# GUAGE.net
KiCad netlist of a schematic drawn in Altium Designer
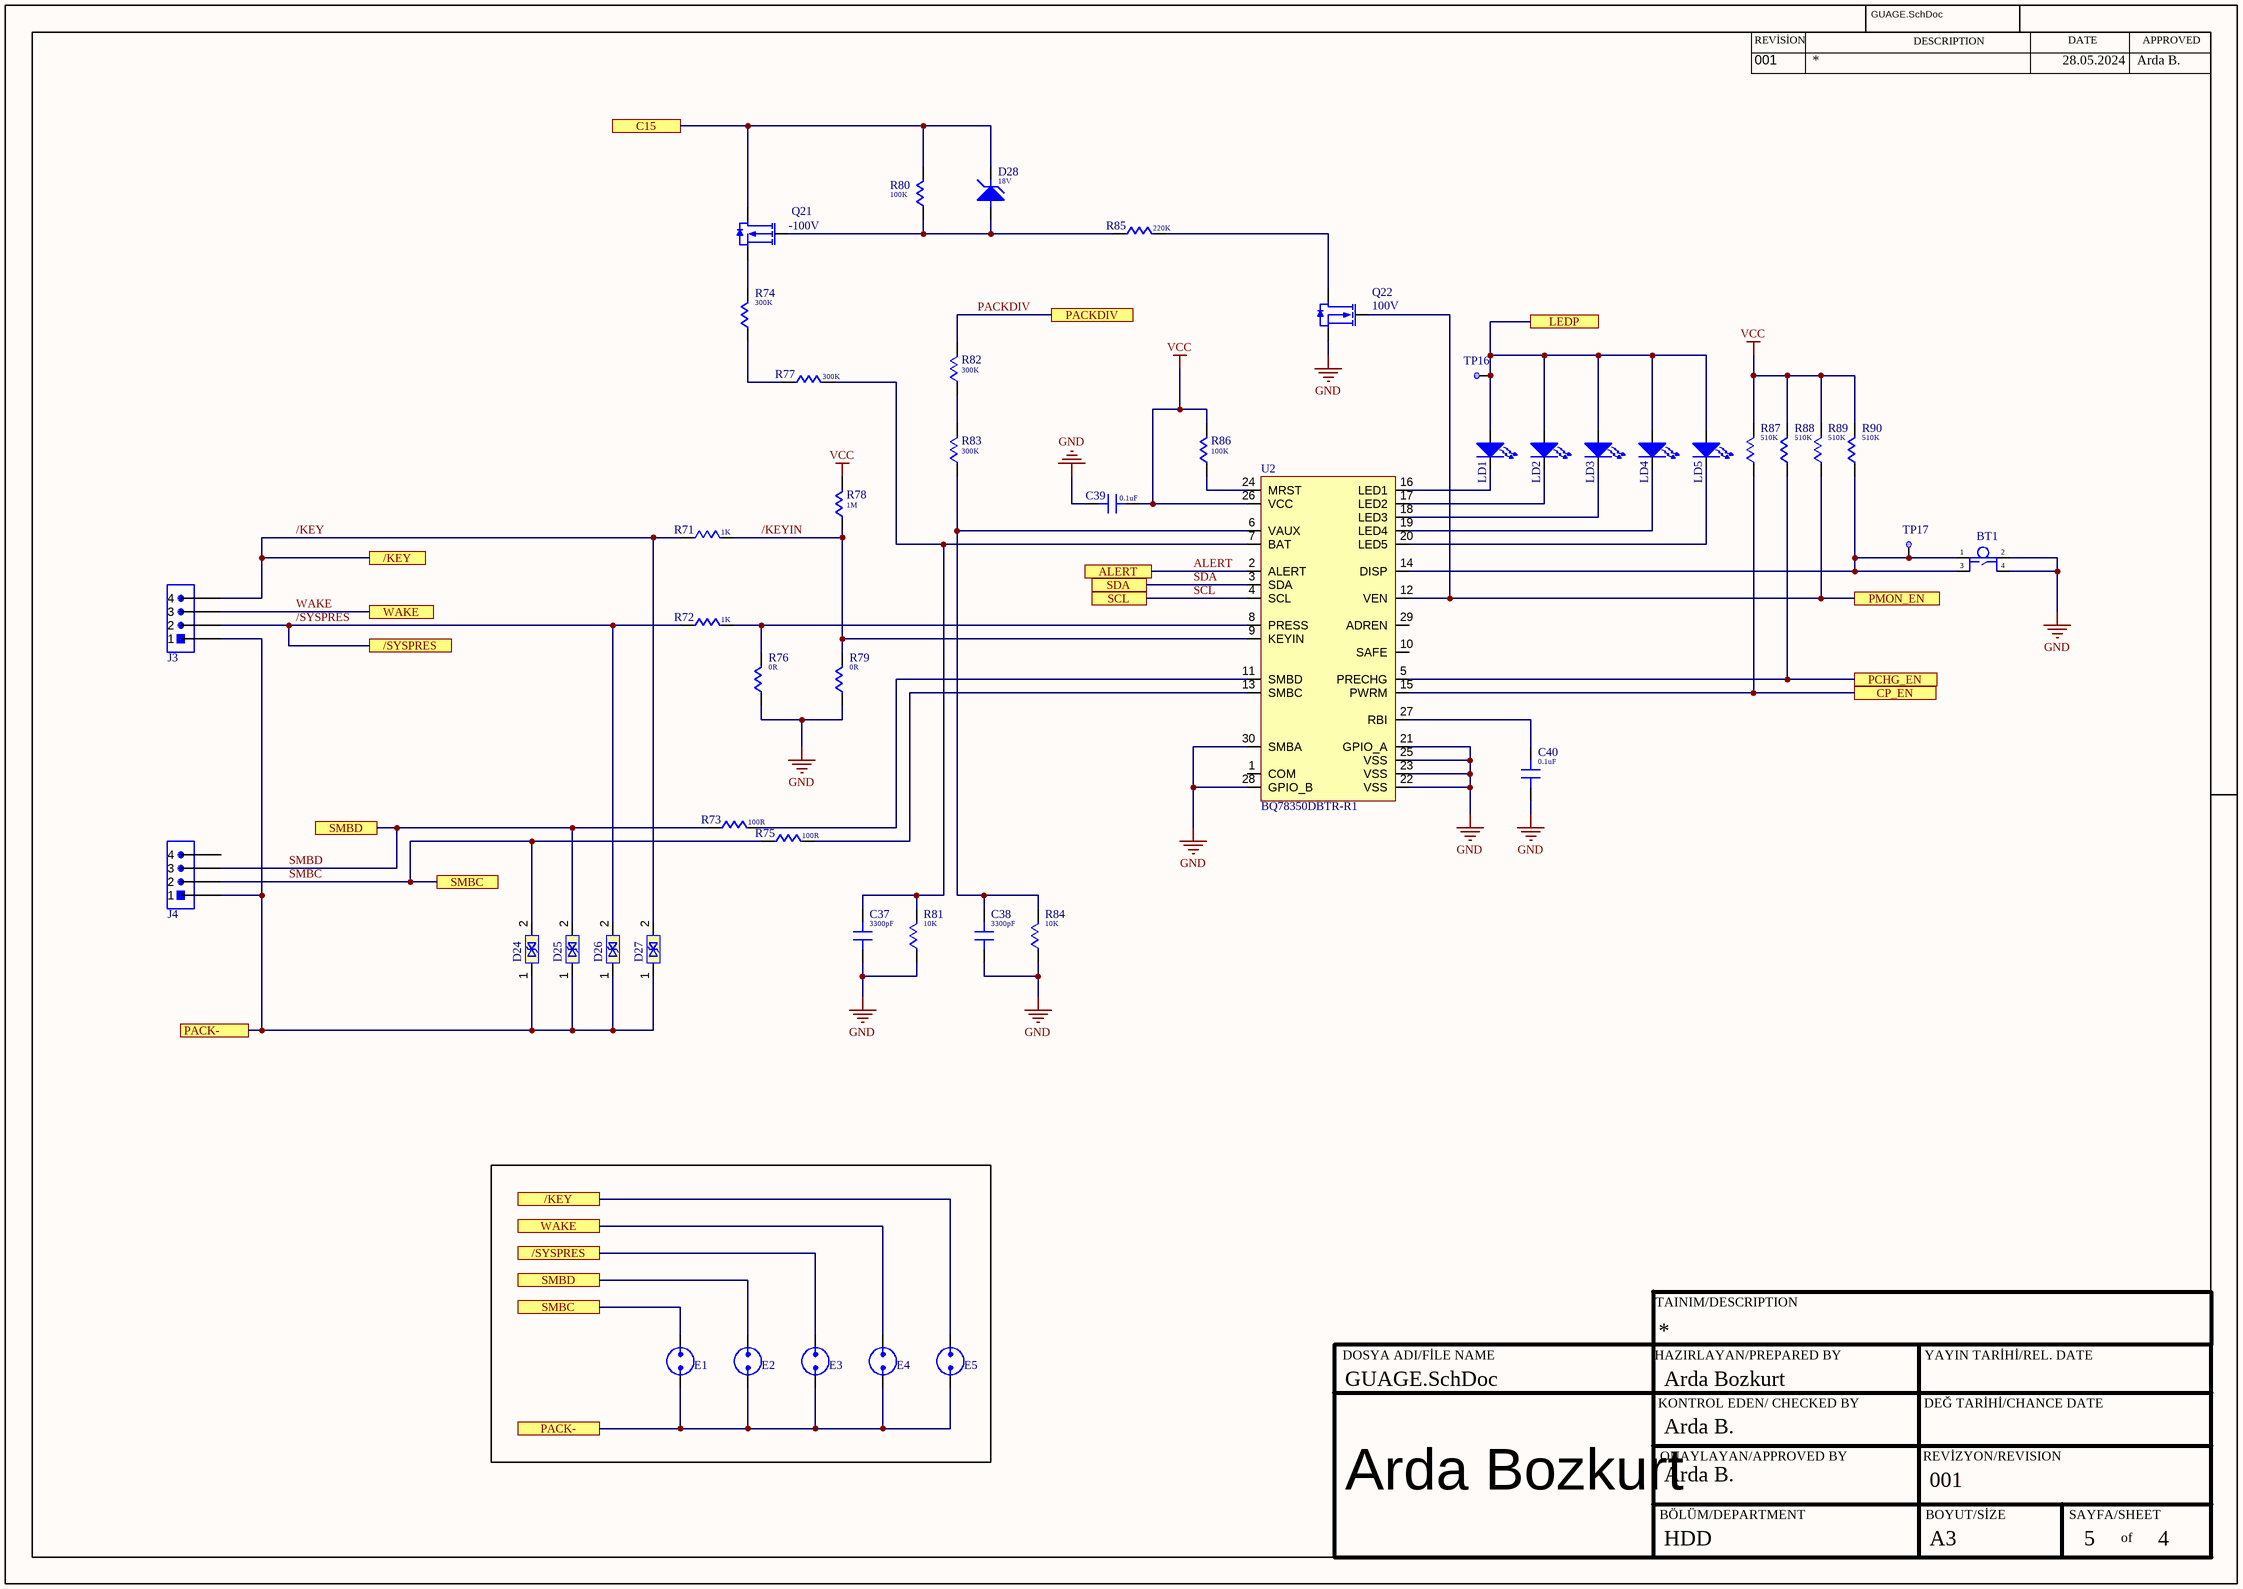
[diagram p0: GUAGE.SchDoc]

(export (version "E")
  (design (tool "Eeschema 10.0.6"))
  (components
    (comp (ref "BT1")
      (value "1977223-6")
      (footprint "BUTTOM")
      (description "Pushbutton Switch, SPST, Momentary, 0.05A, 24VDC, Solder Terminal, Panel Mount")
      (fields
        (field (name "MANUFACTURER") "TE Connectivity")
        (field (name "MANUFACTURER PART NUMBER") "FSM4JSMA")
      )
      (libsource (lib "BMS_Lib") (part "BT_SWITCH_TACTILE_0.05A_24V"))
    )
    (comp (ref "C37")
      (value "3300pF")
      (footprint "C_0603")
      (description "Multilayer Ceramic Capacitor, 0.1 uF, 100 V, ± 10%, X7R, 0603 [1608 Metric]")
      (fields
        (field (name "MANUFACTURER") "Murata")
        (field (name "MANUFACTURER PART NUMBER") "GRM188R72A104KA35D")
      )
      (libsource (lib "BMS_Lib") (part "C_3300pF_0603_25V"))
    )
    (comp (ref "C38")
      (value "3300pF")
      (footprint "C_0603")
      (description "Multilayer Ceramic Capacitor, 0.1 uF, 100 V, ± 10%, X7R, 0603 [1608 Metric]")
      (fields
        (field (name "MANUFACTURER") "Murata")
        (field (name "MANUFACTURER PART NUMBER") "GRM188R72A104KA35D")
      )
      (libsource (lib "BMS_Lib") (part "C_3300pF_0603_25V"))
    )
    (comp (ref "C39")
      (value "0.1uF")
      (footprint "C_0603")
      (description "Ceramic Capacitor, Multilayer, Ceramic, 50V, 10% -Tol, X7R, 15% Tc, 0.1Uf, Surface Mount, 0603")
      (fields
        (field (name "MANUFACTURER") "TDK")
        (field (name "MANUFACTURER PART NUMBER") "C1608X7R1H104K080AA")
      )
      (libsource (lib "BMS_Lib") (part "C_0.1uF_0603_50V"))
    )
    (comp (ref "C40")
      (value "0.1uF")
      (footprint "C_0603")
      (description "Ceramic Capacitor, Multilayer, Ceramic, 50V, 10% -Tol, X7R, 15% Tc, 0.1Uf, Surface Mount, 0603")
      (fields
        (field (name "MANUFACTURER") "TDK")
        (field (name "MANUFACTURER PART NUMBER") "C1608X7R1H104K080AA")
      )
      (libsource (lib "BMS_Lib") (part "C_0.1uF_0603_50V"))
    )
    (comp (ref "D24")
      (value "TPD1E10B06DPYT")
      (footprint "ESD_X1SON")
      (description "12-pF, ±5.5V, ±30-kV ESD protection diode in 0402 and SOD-523 package 2-X1SON -40 to 125")
      (fields (field (name "MANUFACTURER") "Texas Instruments"))
      (libsource (lib "BMS_Lib") (part "ESD_TVS_DİODE_5.5VWM_14VC_2X1SON"))
    )
    (comp (ref "D25")
      (value "TPD1E10B06DPYT")
      (footprint "ESD_X1SON")
      (description "12-pF, ±5.5V, ±30-kV ESD protection diode in 0402 and SOD-523 package 2-X1SON -40 to 125")
      (fields (field (name "MANUFACTURER") "Texas Instruments"))
      (libsource (lib "BMS_Lib") (part "ESD_TVS_DİODE_5.5VWM_14VC_2X1SON"))
    )
    (comp (ref "D26")
      (value "TPD1E10B06DPYT")
      (footprint "ESD_X1SON")
      (description "12-pF, ±5.5V, ±30-kV ESD protection diode in 0402 and SOD-523 package 2-X1SON -40 to 125")
      (fields (field (name "MANUFACTURER") "Texas Instruments"))
      (libsource (lib "BMS_Lib") (part "ESD_TVS_DİODE_5.5VWM_14VC_2X1SON"))
    )
    (comp (ref "D27")
      (value "TPD1E10B06DPYT")
      (footprint "ESD_X1SON")
      (description "12-pF, ±5.5V, ±30-kV ESD protection diode in 0402 and SOD-523 package 2-X1SON -40 to 125")
      (fields (field (name "MANUFACTURER") "Texas Instruments"))
      (libsource (lib "BMS_Lib") (part "ESD_TVS_DİODE_5.5VWM_14VC_2X1SON"))
    )
    (comp (ref "D28")
      (value "18V")
      (footprint "D_SOD323")
      (description "Diode Zener Single 18V 5% 200mW Automotive 2-Pin SOD-323 T/R")
      (fields
        (field (name "MANUFACTURER") "Diodes")
        (field (name "MANUFACTURER PART NUMBER") "MMSZ5248BS-7-F")
      )
      (libsource (lib "BMS_Lib") (part "D_ZENER_18V_SOD323"))
    )
    (comp (ref "E1")
      (value "SPARKGAP")
      (footprint "SPARK_GARP")
      (description "Spark Gap")
      (libsource (lib "BMS_Lib") (part "E_Spark_Gap"))
    )
    (comp (ref "E2")
      (value "SPARKGAP")
      (footprint "SPARK_GARP")
      (description "Spark Gap")
      (libsource (lib "BMS_Lib") (part "E_Spark_Gap"))
    )
    (comp (ref "E3")
      (value "SPARKGAP")
      (footprint "SPARK_GARP")
      (description "Spark Gap")
      (libsource (lib "BMS_Lib") (part "E_Spark_Gap"))
    )
    (comp (ref "E4")
      (value "SPARKGAP")
      (footprint "SPARK_GARP")
      (description "Spark Gap")
      (libsource (lib "BMS_Lib") (part "E_Spark_Gap"))
    )
    (comp (ref "E5")
      (value "SPARKGAP")
      (footprint "SPARK_GARP")
      (description "Spark Gap")
      (libsource (lib "BMS_Lib") (part "E_Spark_Gap"))
    )
    (comp (ref "J3")
      (value "0022053041")
      (footprint "CONN_4")
      (description "KK 254 Solid Header, Right-Angle, with Friction Lock, 4 Circuits, Tin (Sn) Plating")
      (fields (field (name "MANUFACTURER") "Molex") (field (name "MANUFACTURER PART NUMBER") "22-05-3041"))
      (libsource (lib "BMS_Lib") (part "J_CONN_4POS_2.54MM"))
    )
    (comp (ref "J4")
      (value "0022053041")
      (footprint "CONN_4")
      (description "KK 254 Solid Header, Right-Angle, with Friction Lock, 4 Circuits, Tin (Sn) Plating")
      (fields (field (name "MANUFACTURER") "Molex") (field (name "MANUFACTURER PART NUMBER") "22-05-3041"))
      (libsource (lib "BMS_Lib") (part "J_CONN_4POS_2.54MM"))
    )
    (comp (ref "LD1")
      (value "LTST-C190GKT")
      (footprint "LED_0603")
      (description "LED Uni-Color Green 565nm 2-Pin Chip LED T/R")
      (fields (field (name "MANUFACTURER") "Vishay Lite-On") (field (name "VOLTAGE") "2V"))
      (libsource (lib "BMS_Lib") (part "LED_GREEN_0603"))
    )
    (comp (ref "LD2")
      (value "LTST-C190GKT")
      (footprint "LED_0603")
      (description "LED Uni-Color Green 565nm 2-Pin Chip LED T/R")
      (fields (field (name "MANUFACTURER") "Vishay Lite-On") (field (name "VOLTAGE") "2V"))
      (libsource (lib "BMS_Lib") (part "LED_GREEN_0603"))
    )
    (comp (ref "LD3")
      (value "LTST-C190GKT")
      (footprint "LED_0603")
      (description "LED Uni-Color Green 565nm 2-Pin Chip LED T/R")
      (fields (field (name "MANUFACTURER") "Vishay Lite-On") (field (name "VOLTAGE") "2V"))
      (libsource (lib "BMS_Lib") (part "LED_GREEN_0603"))
    )
    (comp (ref "LD4")
      (value "LTST-C190GKT")
      (footprint "LED_0603")
      (description "LED Uni-Color Green 565nm 2-Pin Chip LED T/R")
      (fields (field (name "MANUFACTURER") "Vishay Lite-On") (field (name "VOLTAGE") "2V"))
      (libsource (lib "BMS_Lib") (part "LED_GREEN_0603"))
    )
    (comp (ref "LD5")
      (value "LTST-C190GKT")
      (footprint "LED_0603")
      (description "LED Uni-Color Green 565nm 2-Pin Chip LED T/R")
      (fields (field (name "MANUFACTURER") "Vishay Lite-On") (field (name "VOLTAGE") "2V"))
      (libsource (lib "BMS_Lib") (part "LED_GREEN_0603"))
    )
    (comp (ref "Q21")
      (value "ZXMP10A13FTA")
      (footprint "Q_SOT23-3")
      (description "P-Channel 100 V 1 Ohm Surface Mount Enhancement Mode MOSFET - SOT-23")
      (fields (field (name "MANUFACTURER") "Diodes Zetex") (field (name "VOLTAGE RATING (DC)") "-100V"))
      (libsource (lib "BMS_Lib") (part "Q_MOSFET_100V_SOT23-3_1"))
    )
    (comp (ref "Q22")
      (value "BSS123")
      (footprint "Q_SOT23-3")
      (description "Transistor MOSFET Negative Channel 100 Volt 0.17A 3-Pin SOT-23")
      (fields (field (name "MANUFACTURER") "ON Semiconductor / Fairchild") (field (name "VOLTAGE") "100V"))
      (libsource (lib "BMS_Lib") (part "Q_MOSFET_100V_SOT23-3"))
    )
    (comp (ref "R71")
      (value "1K")
      (footprint "R_0603")
      (description "SMD Chip Resistor, 1 kOhm, ± 5%, 100 mW, 0603 [1608 Metric], Thick Film, General Purpose")
      (fields
        (field (name "MANUFACTURER") "Vishay Dale")
        (field (name "MANUFACTURER PART NUMBER") "CRCW06031K00JNEA")
      )
      (libsource (lib "BMS_Lib") (part "R_1K_%5_1/10W_0603"))
    )
    (comp (ref "R72")
      (value "1K")
      (footprint "R_0603")
      (description "SMD Chip Resistor, 1 kOhm, ± 5%, 100 mW, 0603 [1608 Metric], Thick Film, General Purpose")
      (fields
        (field (name "MANUFACTURER") "Vishay Dale")
        (field (name "MANUFACTURER PART NUMBER") "CRCW06031K00JNEA")
      )
      (libsource (lib "BMS_Lib") (part "R_1K_%5_1/10W_0603"))
    )
    (comp (ref "R73")
      (value "100R")
      (footprint "R_0603")
      (description "SMD Chip Resistor, 100 Ohm, ± 5%, 100 mW, 0603 [1608 Metric], Thick Film, General Purpose")
      (fields
        (field (name "MANUFACTURER") "Vishay Dale")
        (field (name "MANUFACTURER PART NUMBER") "CRCW0603100RJNEA")
      )
      (libsource (lib "BMS_Lib") (part "R_100OHM_%5_1/10W_0603"))
    )
    (comp (ref "R74")
      (value "300K")
      (footprint "R_0603")
      (description "Res Thin Film 0603 300K Ohm 0.1% 0.1W(1/10W) ±25ppm/C Sulfur Resistant Pad SMD Automotive T/R")
      (fields
        (field (name "MANUFACTURER") "Susumu")
        (field (name "MANUFACTURER PART NUMBER") "RG1608P-304-B-T5")
      )
      (libsource (lib "BMS_Lib") (part "R_300K_%0.1_1/10W_0603"))
    )
    (comp (ref "R75")
      (value "100R")
      (footprint "R_0603")
      (description "SMD Chip Resistor, 100 Ohm, ± 5%, 100 mW, 0603 [1608 Metric], Thick Film, General Purpose")
      (fields
        (field (name "MANUFACTURER") "Vishay Dale")
        (field (name "MANUFACTURER PART NUMBER") "CRCW0603100RJNEA")
      )
      (libsource (lib "BMS_Lib") (part "R_100OHM_%5_1/10W_0603"))
    )
    (comp (ref "R76")
      (value "0R")
      (footprint "R_0603")
      (description "Zero Ohm Resistor, Jumper, 0603 [1608 Metric], Thick Film, 330 mW, 5 A, Surface Mount")
      (fields
        (field (name "MANUFACTURER") "Vishay Dale")
        (field (name "MANUFACTURER PART NUMBER") "CRCW06030000Z0EAHP")
      )
      (libsource (lib "BMS_Lib") (part "R_0OHM_1/10W_0603"))
    )
    (comp (ref "R77")
      (value "300K")
      (footprint "R_0603")
      (description "Res Thin Film 0603 300K Ohm 0.1% 0.1W(1/10W) ±25ppm/C Sulfur Resistant Pad SMD Automotive T/R")
      (fields
        (field (name "MANUFACTURER") "Susumu")
        (field (name "MANUFACTURER PART NUMBER") "RG1608P-304-B-T5")
      )
      (libsource (lib "BMS_Lib") (part "R_300K_%0.1_1/10W_0603"))
    )
    (comp (ref "R78")
      (value "1M")
      (footprint "R_0603")
      (description "SMD Chip Resistor, 1 MOhm, ± 5%, 100 mW, 0603 [1608 Metric], Thick Film, General Purpose")
      (fields
        (field (name "MANUFACTURER") "Vishay Dale")
        (field (name "MANUFACTURER PART NUMBER") "CRCW06031M00JNEA")
      )
      (libsource (lib "BMS_Lib") (part "R_1M_%5_1/10W_0603"))
    )
    (comp (ref "R79")
      (value "0R")
      (footprint "R_0603")
      (description "Zero Ohm Resistor, Jumper, 0603 [1608 Metric], Thick Film, 330 mW, 5 A, Surface Mount")
      (fields
        (field (name "MANUFACTURER") "Vishay Dale")
        (field (name "MANUFACTURER PART NUMBER") "CRCW06030000Z0EAHP")
      )
      (libsource (lib "BMS_Lib") (part "R_0OHM_1/10W_0603"))
    )
    (comp (ref "R80")
      (value "100K")
      (footprint "R_0603")
      (description "SMD Chip Resistor, 100 kOhm, ± 5%, 100 mW, 0603 [1608 Metric], Thick Film, General Purpose")
      (fields
        (field (name "MANUFACTURER") "Vishay")
        (field (name "MANUFACTURER PART NUMBER") "CRCW0603100KJNEA")
      )
      (libsource (lib "BMS_Lib") (part "R_100K_%5_1/10W_0603"))
    )
    (comp (ref "R81")
      (value "10K")
      (footprint "R_0603")
      (description "Res Thin Film 0603 10K Ohm 0.1% 0.1W(1/10W) ±25ppm/C Sulfur Resistant Pad SMD Automotive T/R")
      (fields
        (field (name "MANUFACTURER") "Susumu")
        (field (name "MANUFACTURER PART NUMBER") "RG1608P-103-B-T5")
      )
      (libsource (lib "BMS_Lib") (part "R_10K_%0.1_1/10W_0603"))
    )
    (comp (ref "R82")
      (value "300K")
      (footprint "R_0603")
      (description "Res Thin Film 0603 300K Ohm 0.1% 0.1W(1/10W) ±25ppm/C Sulfur Resistant Pad SMD Automotive T/R")
      (fields
        (field (name "MANUFACTURER") "Susumu")
        (field (name "MANUFACTURER PART NUMBER") "RG1608P-304-B-T5")
      )
      (libsource (lib "BMS_Lib") (part "R_300K_%0.1_1/10W_0603"))
    )
    (comp (ref "R83")
      (value "300K")
      (footprint "R_0603")
      (description "Res Thin Film 0603 300K Ohm 0.1% 0.1W(1/10W) ±25ppm/C Sulfur Resistant Pad SMD Automotive T/R")
      (fields
        (field (name "MANUFACTURER") "Susumu")
        (field (name "MANUFACTURER PART NUMBER") "RG1608P-304-B-T5")
      )
      (libsource (lib "BMS_Lib") (part "R_300K_%0.1_1/10W_0603"))
    )
    (comp (ref "R84")
      (value "10K")
      (footprint "R_0603")
      (description "Res Thin Film 0603 10K Ohm 0.1% 0.1W(1/10W) ±25ppm/C Sulfur Resistant Pad SMD Automotive T/R")
      (fields
        (field (name "MANUFACTURER") "Susumu")
        (field (name "MANUFACTURER PART NUMBER") "RG1608P-103-B-T5")
      )
      (libsource (lib "BMS_Lib") (part "R_10K_%0.1_1/10W_0603"))
    )
    (comp (ref "R85")
      (value "220K")
      (footprint "R_0603")
      (description "SMD Chip Resistor, 220 kOhm, ± 5%, 100 mW, 0603 [1608 Metric], Thick Film, General Purpose")
      (fields
        (field (name "MANUFACTURER") "Vishay Dale")
        (field (name "MANUFACTURER PART NUMBER") "CRCW0603220KJNEA")
      )
      (libsource (lib "BMS_Lib") (part "R_220K_%5_1/10W_0603"))
    )
    (comp (ref "R86")
      (value "100K")
      (footprint "R_0603")
      (description "SMD Chip Resistor, 100 kOhm, ± 5%, 100 mW, 0603 [1608 Metric], Thick Film, General Purpose")
      (fields
        (field (name "MANUFACTURER") "Vishay")
        (field (name "MANUFACTURER PART NUMBER") "CRCW0603100KJNEA")
      )
      (libsource (lib "BMS_Lib") (part "R_100K_%5_1/10W_0603"))
    )
    (comp (ref "R87")
      (value "510K")
      (footprint "R_0603")
      (description "SMD Chip Resistor, 510 kOhm, ± 5%, 100 mW, 0603 [1608 Metric], Thick Film, General Purpose")
      (fields
        (field (name "MANUFACTURER") "Vishay Dale")
        (field (name "MANUFACTURER PART NUMBER") "CRCW0603510KJNEA")
      )
      (libsource (lib "BMS_Lib") (part "R_510K_%5_1/10W_0603"))
    )
    (comp (ref "R88")
      (value "510K")
      (footprint "R_0603")
      (description "SMD Chip Resistor, 510 kOhm, ± 5%, 100 mW, 0603 [1608 Metric], Thick Film, General Purpose")
      (fields
        (field (name "MANUFACTURER") "Vishay Dale")
        (field (name "MANUFACTURER PART NUMBER") "CRCW0603510KJNEA")
      )
      (libsource (lib "BMS_Lib") (part "R_510K_%5_1/10W_0603"))
    )
    (comp (ref "R89")
      (value "510K")
      (footprint "R_0603")
      (description "SMD Chip Resistor, 510 kOhm, ± 5%, 100 mW, 0603 [1608 Metric], Thick Film, General Purpose")
      (fields
        (field (name "MANUFACTURER") "Vishay Dale")
        (field (name "MANUFACTURER PART NUMBER") "CRCW0603510KJNEA")
      )
      (libsource (lib "BMS_Lib") (part "R_510K_%5_1/10W_0603"))
    )
    (comp (ref "R90")
      (value "510K")
      (footprint "R_0603")
      (description "SMD Chip Resistor, 510 kOhm, ± 5%, 100 mW, 0603 [1608 Metric], Thick Film, General Purpose")
      (fields
        (field (name "MANUFACTURER") "Vishay Dale")
        (field (name "MANUFACTURER PART NUMBER") "CRCW0603510KJNEA")
      )
      (libsource (lib "BMS_Lib") (part "R_510K_%5_1/10W_0603"))
    )
    (comp (ref "TP16")
      (value "5011")
      (footprint "TP_VİA")
      (fields (field (name "MANUFACTURER") "Keystone Electronics"))
      (libsource (lib "BMS_Lib") (part "TP_PC_TEST_POİNT"))
    )
    (comp (ref "TP17")
      (value "5011")
      (footprint "TP_VİA")
      (fields (field (name "MANUFACTURER") "Keystone Electronics"))
      (libsource (lib "BMS_Lib") (part "TP_PC_TEST_POİNT"))
    )
    (comp (ref "U2")
      (value "BQ78350DBTR-R1")
      (footprint "30TSSOP")
      (description "Battery Management Controller/Fuel Gauge Li-Ion/Li-Pol/LiFePO4 5.5V 30-Pin TSSOP T/R")
      (fields (field (name "MANUFACTURER") "Texas Instruments"))
      (libsource (lib "BMS_Lib") (part "GUAGE_IC_30TSSOP"))
    )
  )
  (nets
    (net (code "1") (name "/ALERT") (class "Default")
      (node (ref "U2") (pin "2") (pinfunction "ALERT_2") (pintype "passive"))
    )
    (net (code "2") (name "/C15") (class "Default")
      (node (ref "D28") (pin "1") (pinfunction "1_1") (pintype "passive"))
      (node (ref "Q21") (pin "2") (pinfunction "S_2") (pintype "passive"))
      (node (ref "R80") (pin "2") (pinfunction "2_2") (pintype "passive"))
    )
    (net (code "3") (name "/CP_EN") (class "Default")
      (node (ref "R87") (pin "1") (pinfunction "1_1") (pintype "passive"))
      (node (ref "U2") (pin "15") (pinfunction "PWRM_15") (pintype "passive"))
    )
    (net (code "4") (name "/LEDP") (class "Default")
      (node (ref "LD1") (pin "2") (pinfunction "2_2") (pintype "passive"))
      (node (ref "LD2") (pin "2") (pinfunction "2_2") (pintype "passive"))
      (node (ref "LD3") (pin "2") (pinfunction "2_2") (pintype "passive"))
      (node (ref "LD4") (pin "2") (pinfunction "2_2") (pintype "passive"))
      (node (ref "LD5") (pin "2") (pinfunction "2_2") (pintype "passive"))
      (node (ref "TP16") (pin "1") (pinfunction "1_1") (pintype "passive"))
    )
    (net (code "5") (name "/PACK-") (class "Default")
      (node (ref "D24") (pin "1") (pinfunction "1_1") (pintype "passive"))
      (node (ref "D25") (pin "1") (pinfunction "1_1") (pintype "passive"))
      (node (ref "D26") (pin "1") (pinfunction "1_1") (pintype "passive"))
      (node (ref "D27") (pin "1") (pinfunction "1_1") (pintype "passive"))
      (node (ref "E1") (pin "2") (pinfunction "2_2") (pintype "passive"))
      (node (ref "E2") (pin "2") (pinfunction "2_2") (pintype "passive"))
      (node (ref "E3") (pin "2") (pinfunction "2_2") (pintype "passive"))
      (node (ref "E4") (pin "2") (pinfunction "2_2") (pintype "passive"))
      (node (ref "E5") (pin "2") (pinfunction "2_2") (pintype "passive"))
      (node (ref "J3") (pin "1") (pinfunction "1_1") (pintype "passive"))
      (node (ref "J4") (pin "1") (pinfunction "1_1") (pintype "passive"))
    )
    (net (code "6") (name "/PACKDIV") (class "Default")
      (node (ref "R82") (pin "2") (pinfunction "2_2") (pintype "passive"))
    )
    (net (code "7") (name "/PCHG_EN") (class "Default")
      (node (ref "R88") (pin "1") (pinfunction "1_1") (pintype "passive"))
      (node (ref "U2") (pin "5") (pinfunction "PRECHG_5") (pintype "passive"))
    )
    (net (code "8") (name "/PMON_EN") (class "Default")
      (node (ref "Q22") (pin "1") (pinfunction "G_1") (pintype "passive"))
      (node (ref "R89") (pin "1") (pinfunction "1_1") (pintype "passive"))
      (node (ref "U2") (pin "12") (pinfunction "VEN_12") (pintype "passive"))
    )
    (net (code "9") (name "/SCL") (class "Default")
      (node (ref "U2") (pin "4") (pinfunction "SCL_4") (pintype "passive"))
    )
    (net (code "10") (name "/SDA") (class "Default")
      (node (ref "U2") (pin "3") (pinfunction "SDA_3") (pintype "passive"))
    )
    (net (code "11") (name "/SMBC") (class "Default")
      (node (ref "D24") (pin "2") (pinfunction "2_2") (pintype "passive"))
      (node (ref "E1") (pin "1") (pinfunction "1_1") (pintype "passive"))
      (node (ref "J4") (pin "2") (pinfunction "2_2") (pintype "passive"))
      (node (ref "R75") (pin "1") (pinfunction "1_1") (pintype "passive"))
    )
    (net (code "12") (name "/SMBD") (class "Default")
      (node (ref "D25") (pin "2") (pinfunction "2_2") (pintype "passive"))
      (node (ref "E2") (pin "1") (pinfunction "1_1") (pintype "passive"))
      (node (ref "J4") (pin "3") (pinfunction "3_3") (pintype "passive"))
      (node (ref "R73") (pin "1") (pinfunction "1_1") (pintype "passive"))
    )
    (net (code "13") (name "/WAKE") (class "Default")
      (node (ref "E4") (pin "1") (pinfunction "1_1") (pintype "passive"))
      (node (ref "J3") (pin "3") (pinfunction "3_3") (pintype "passive"))
    )
    (net (code "14") (name "/{slash}KEY") (class "Default")
      (node (ref "D27") (pin "2") (pinfunction "2_2") (pintype "passive"))
      (node (ref "E5") (pin "1") (pinfunction "1_1") (pintype "passive"))
      (node (ref "J3") (pin "4") (pinfunction "4_4") (pintype "passive"))
      (node (ref "R71") (pin "1") (pinfunction "1_1") (pintype "passive"))
    )
    (net (code "15") (name "/{slash}KEYIN") (class "Default")
      (node (ref "R71") (pin "2") (pinfunction "2_2") (pintype "passive"))
      (node (ref "R78") (pin "1") (pinfunction "1_1") (pintype "passive"))
      (node (ref "R79") (pin "2") (pinfunction "2_2") (pintype "passive"))
      (node (ref "U2") (pin "9") (pinfunction "KEYIN_9") (pintype "passive"))
    )
    (net (code "16") (name "/{slash}SYSPRES") (class "Default")
      (node (ref "D26") (pin "2") (pinfunction "2_2") (pintype "passive"))
      (node (ref "E3") (pin "1") (pinfunction "1_1") (pintype "passive"))
      (node (ref "J3") (pin "2") (pinfunction "2_2") (pintype "passive"))
      (node (ref "R72") (pin "1") (pinfunction "1_1") (pintype "passive"))
    )
    (net (code "17") (name "GND") (class "Default")
      (node (ref "BT1") (pin "2") (pinfunction "2_2") (pintype "passive"))
      (node (ref "BT1") (pin "4") (pinfunction "4_4") (pintype "passive"))
      (node (ref "C37") (pin "1") (pinfunction "1_1") (pintype "passive"))
      (node (ref "C38") (pin "1") (pinfunction "1_1") (pintype "passive"))
      (node (ref "C39") (pin "1") (pinfunction "1_1") (pintype "passive"))
      (node (ref "C40") (pin "1") (pinfunction "1_1") (pintype "passive"))
      (node (ref "Q22") (pin "2") (pinfunction "S_2") (pintype "passive"))
      (node (ref "R76") (pin "1") (pinfunction "1_1") (pintype "passive"))
      (node (ref "R79") (pin "1") (pinfunction "1_1") (pintype "passive"))
      (node (ref "R81") (pin "1") (pinfunction "1_1") (pintype "passive"))
      (node (ref "R84") (pin "1") (pinfunction "1_1") (pintype "passive"))
      (node (ref "U2") (pin "21") (pinfunction "GPIO_A_21") (pintype "passive"))
      (node (ref "U2") (pin "22") (pinfunction "VSS_22") (pintype "passive"))
      (node (ref "U2") (pin "23") (pinfunction "VSS_23") (pintype "passive"))
      (node (ref "U2") (pin "25") (pinfunction "VSS_25") (pintype "passive"))
      (node (ref "U2") (pin "28") (pinfunction "GPIO_B_28") (pintype "passive"))
      (node (ref "U2") (pin "30") (pinfunction "SMBA_30") (pintype "passive"))
    )
    (net (code "18") (name "Net-(Q21-D)") (class "Default")
      (node (ref "Q21") (pin "3") (pinfunction "D_3") (pintype "passive"))
      (node (ref "R74") (pin "2") (pinfunction "2_2") (pintype "passive"))
    )
    (net (code "19") (name "Net-(Q21-G)") (class "Default")
      (node (ref "D28") (pin "2") (pinfunction "2_2") (pintype "passive"))
      (node (ref "Q21") (pin "1") (pinfunction "G_1") (pintype "passive"))
      (node (ref "R80") (pin "1") (pinfunction "1_1") (pintype "passive"))
      (node (ref "R85") (pin "1") (pinfunction "1_1") (pintype "passive"))
    )
    (net (code "20") (name "Net-(Q22-D)") (class "Default")
      (node (ref "Q22") (pin "3") (pinfunction "D_3") (pintype "passive"))
      (node (ref "R85") (pin "2") (pinfunction "2_2") (pintype "passive"))
    )
    (net (code "21") (name "Net-(R74-Pad1)") (class "Default")
      (node (ref "R74") (pin "1") (pinfunction "1_1") (pintype "passive"))
      (node (ref "R77") (pin "1") (pinfunction "1_1") (pintype "passive"))
    )
    (net (code "22") (name "Net-(R82-Pad1)") (class "Default")
      (node (ref "R82") (pin "1") (pinfunction "1_1") (pintype "passive"))
      (node (ref "R83") (pin "2") (pinfunction "2_2") (pintype "passive"))
    )
    (net (code "23") (name "Net-(U2-BAT)") (class "Default")
      (node (ref "C37") (pin "2") (pinfunction "2_2") (pintype "passive"))
      (node (ref "R77") (pin "2") (pinfunction "2_2") (pintype "passive"))
      (node (ref "R81") (pin "2") (pinfunction "2_2") (pintype "passive"))
      (node (ref "U2") (pin "7") (pinfunction "BAT_7") (pintype "passive"))
    )
    (net (code "24") (name "Net-(U2-DISP)") (class "Default")
      (node (ref "BT1") (pin "1") (pinfunction "1_1") (pintype "passive"))
      (node (ref "BT1") (pin "3") (pinfunction "3_3") (pintype "passive"))
      (node (ref "R90") (pin "1") (pinfunction "1_1") (pintype "passive"))
      (node (ref "TP17") (pin "1") (pinfunction "1_1") (pintype "passive"))
      (node (ref "U2") (pin "14") (pinfunction "DISP_14") (pintype "passive"))
    )
    (net (code "25") (name "Net-(U2-LED1)") (class "Default")
      (node (ref "LD1") (pin "1") (pinfunction "1_1") (pintype "passive"))
      (node (ref "U2") (pin "16") (pinfunction "LED1_16") (pintype "passive"))
    )
    (net (code "26") (name "Net-(U2-LED2)") (class "Default")
      (node (ref "LD2") (pin "1") (pinfunction "1_1") (pintype "passive"))
      (node (ref "U2") (pin "17") (pinfunction "LED2_17") (pintype "passive"))
    )
    (net (code "27") (name "Net-(U2-LED3)") (class "Default")
      (node (ref "LD3") (pin "1") (pinfunction "1_1") (pintype "passive"))
      (node (ref "U2") (pin "18") (pinfunction "LED3_18") (pintype "passive"))
    )
    (net (code "28") (name "Net-(U2-LED4)") (class "Default")
      (node (ref "LD4") (pin "1") (pinfunction "1_1") (pintype "passive"))
      (node (ref "U2") (pin "19") (pinfunction "LED4_19") (pintype "passive"))
    )
    (net (code "29") (name "Net-(U2-LED5)") (class "Default")
      (node (ref "LD5") (pin "1") (pinfunction "1_1") (pintype "passive"))
      (node (ref "U2") (pin "20") (pinfunction "LED5_20") (pintype "passive"))
    )
    (net (code "30") (name "Net-(U2-MRST)") (class "Default")
      (node (ref "R86") (pin "1") (pinfunction "1_1") (pintype "passive"))
      (node (ref "U2") (pin "24") (pinfunction "MRST_24") (pintype "passive"))
    )
    (net (code "31") (name "Net-(U2-PRESS)") (class "Default")
      (node (ref "R72") (pin "2") (pinfunction "2_2") (pintype "passive"))
      (node (ref "R76") (pin "2") (pinfunction "2_2") (pintype "passive"))
      (node (ref "U2") (pin "8") (pinfunction "PRESS_8") (pintype "passive"))
    )
    (net (code "32") (name "Net-(U2-RBI)") (class "Default")
      (node (ref "C40") (pin "2") (pinfunction "2_2") (pintype "passive"))
      (node (ref "U2") (pin "27") (pinfunction "RBI_27") (pintype "passive"))
    )
    (net (code "33") (name "Net-(U2-SMBC)") (class "Default")
      (node (ref "R75") (pin "2") (pinfunction "2_2") (pintype "passive"))
      (node (ref "U2") (pin "13") (pinfunction "SMBC_13") (pintype "passive"))
    )
    (net (code "34") (name "Net-(U2-SMBD)") (class "Default")
      (node (ref "R73") (pin "2") (pinfunction "2_2") (pintype "passive"))
      (node (ref "U2") (pin "11") (pinfunction "SMBD_11") (pintype "passive"))
    )
    (net (code "35") (name "Net-(U2-VAUX)") (class "Default")
      (node (ref "C38") (pin "2") (pinfunction "2_2") (pintype "passive"))
      (node (ref "R83") (pin "1") (pinfunction "1_1") (pintype "passive"))
      (node (ref "R84") (pin "2") (pinfunction "2_2") (pintype "passive"))
      (node (ref "U2") (pin "6") (pinfunction "VAUX_6") (pintype "passive"))
    )
    (net (code "36") (name "VCC") (class "Default")
      (node (ref "C39") (pin "2") (pinfunction "2_2") (pintype "passive"))
      (node (ref "R78") (pin "2") (pinfunction "2_2") (pintype "passive"))
      (node (ref "R86") (pin "2") (pinfunction "2_2") (pintype "passive"))
      (node (ref "R87") (pin "2") (pinfunction "2_2") (pintype "passive"))
      (node (ref "R88") (pin "2") (pinfunction "2_2") (pintype "passive"))
      (node (ref "R89") (pin "2") (pinfunction "2_2") (pintype "passive"))
      (node (ref "R90") (pin "2") (pinfunction "2_2") (pintype "passive"))
      (node (ref "U2") (pin "26") (pinfunction "VCC_26") (pintype "passive"))
    )
    (net (code "37") (name "unconnected-(J4-Pad4)") (class "Default")
      (node (ref "J4") (pin "4") (pinfunction "4_4") (pintype "passive"))
    )
    (net (code "38") (name "unconnected-(U2-ADREN-Pad29)") (class "Default")
      (node (ref "U2") (pin "29") (pinfunction "ADREN_29") (pintype "passive"))
    )
    (net (code "39") (name "unconnected-(U2-COM-Pad1)") (class "Default")
      (node (ref "U2") (pin "1") (pinfunction "COM_1") (pintype "passive"))
    )
    (net (code "40") (name "unconnected-(U2-SAFE-Pad10)") (class "Default")
      (node (ref "U2") (pin "10") (pinfunction "SAFE_10") (pintype "passive"))
    )
  )
)
